# 2_4_LCD-CL24CR492-37B.net
KiCad netlist of a schematic drawn in Altium Designer
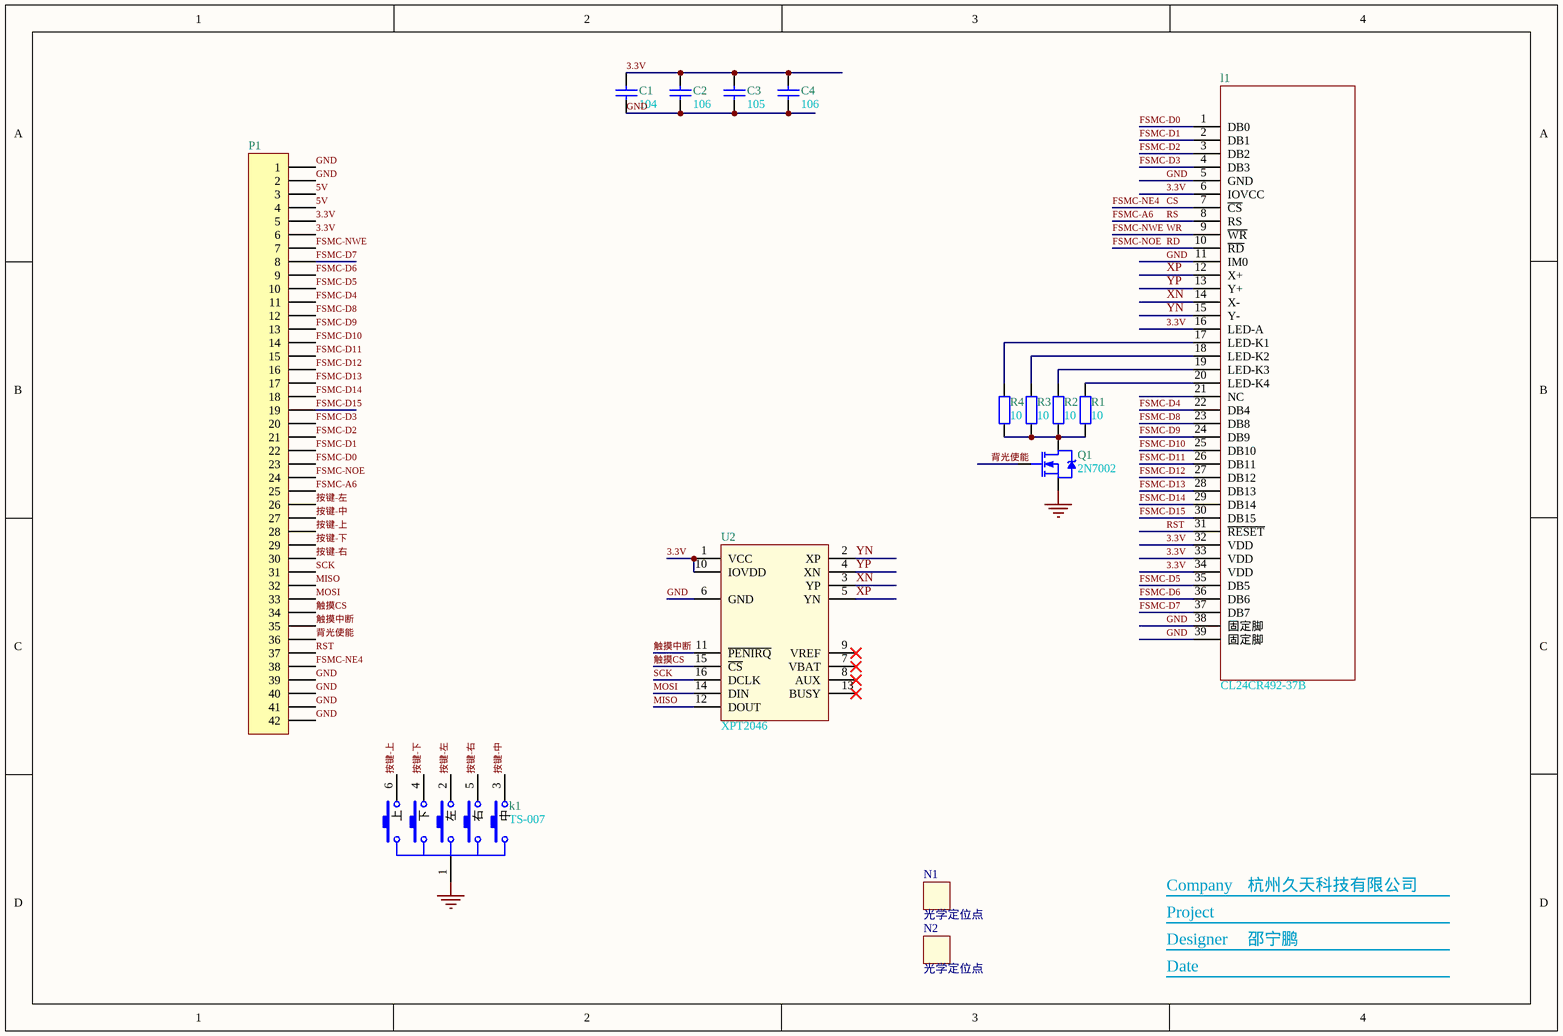
[diagram p0: 2.4寸LCD-CL24CR492-37B.SchDoc]

(export (version "E")
  (design (tool "Eeschema 10.0.6"))
  (components
    (comp (ref "C1")
      (value "104")
      (footprint "C-0603")
      (description "0805")
      (fields (field (name "PUBLISHER") "Altium Limited"))
      (libsource (lib "2电容-V1.0") (part "Cap-0603"))
    )
    (comp (ref "C2")
      (value "106")
      (footprint "C-0603")
      (description "0805")
      (fields (field (name "PUBLISHER") "Altium Limited"))
      (libsource (lib "2电容-V1.0") (part "Cap-0603"))
    )
    (comp (ref "C3")
      (value "105")
      (footprint "C-0603")
      (description "0805")
      (fields (field (name "PUBLISHER") "Altium Limited"))
      (libsource (lib "2电容-V1.0") (part "Cap-0603"))
    )
    (comp (ref "C4")
      (value "106")
      (footprint "C-0603")
      (description "0805")
      (fields (field (name "PUBLISHER") "Altium Limited"))
      (libsource (lib "2电容-V1.0") (part "Cap-0603"))
    )
    (comp (ref "k1")
      (value "TS-007")
      (footprint "TS-007")
      (description "五向开关")
      (libsource (lib "开关-V1") (part "TS-007"))
    )
    (comp (ref "l1")
      (value "CL24CR492-37B")
      (footprint "CL24CR492-37B")
      (libsource (lib "7显示屏-V1.0") (part "CL24CR492-37B"))
    )
    (comp (ref "N1") (value "光学定位点") (footprint "MARK-1mm-3mm") (libsource (lib "11其他元件-V1.0") (part "无引脚")))
    (comp (ref "N2") (value "光学定位点") (footprint "MARK-1mm-3mm") (libsource (lib "11其他元件-V1.0") (part "无引脚")))
    (comp (ref "P1")
      (value "~")
      (footprint "FPC-0.5mm_40P下接翻盖")
      (libsource (lib "5排针-V1.0") (part "MHDR1X42"))
    )
    (comp (ref "Q1") (value "2N7002") (footprint "SOT-23") (libsource (lib "4二极管-V1.1") (part "2N7002")))
    (comp (ref "R1")
      (value "10")
      (footprint "R-0603")
      (description "0603")
      (fields (field (name "PUBLISHER") "Altium Limited"))
      (libsource (lib "1电阻-V1.0") (part "Res2-0603"))
    )
    (comp (ref "R2")
      (value "10")
      (footprint "R-0603")
      (description "0603")
      (fields (field (name "PUBLISHER") "Altium Limited"))
      (libsource (lib "1电阻-V1.0") (part "Res2-0603"))
    )
    (comp (ref "R3")
      (value "10")
      (footprint "R-0603")
      (description "0603")
      (fields (field (name "PUBLISHER") "Altium Limited"))
      (libsource (lib "1电阻-V1.0") (part "Res2-0603"))
    )
    (comp (ref "R4")
      (value "10")
      (footprint "R-0603")
      (description "0603")
      (fields (field (name "PUBLISHER") "Altium Limited"))
      (libsource (lib "1电阻-V1.0") (part "Res2-0603"))
    )
    (comp (ref "U2") (value "XPT2046") (footprint "TSSOP-16") (libsource (lib "8集成电路-V1.1") (part "XPT2046")))
  )
  (nets
    (net (code "1") (name "/3.3V") (class "Default")
      (node (ref "C1") (pin "2") (pinfunction "2_2") (pintype "passive"))
      (node (ref "C2") (pin "2") (pinfunction "2_2") (pintype "passive"))
      (node (ref "C3") (pin "2") (pinfunction "2_2") (pintype "passive"))
      (node (ref "C4") (pin "2") (pinfunction "2_2") (pintype "passive"))
      (node (ref "P1") (pin "5") (pinfunction "5_5") (pintype "passive"))
      (node (ref "P1") (pin "6") (pinfunction "6_6") (pintype "passive"))
      (node (ref "U2") (pin "1") (pinfunction "VCC_1") (pintype "passive"))
      (node (ref "U2") (pin "10") (pinfunction "IOVDD_10") (pintype "passive"))
      (node (ref "l1") (pin "16") (pinfunction "LED-A_16") (pintype "passive"))
      (node (ref "l1") (pin "32") (pinfunction "VDD_32") (pintype "passive"))
      (node (ref "l1") (pin "33") (pinfunction "VDD_33") (pintype "passive"))
      (node (ref "l1") (pin "34") (pinfunction "VDD_34") (pintype "passive"))
      (node (ref "l1") (pin "6") (pinfunction "IOVCC_6") (pintype "passive"))
    )
    (net (code "2") (name "/5V") (class "Default")
      (node (ref "P1") (pin "3") (pinfunction "3_3") (pintype "passive"))
      (node (ref "P1") (pin "4") (pinfunction "4_4") (pintype "passive"))
    )
    (net (code "3") (name "/CS") (class "Default")
      (node (ref "P1") (pin "38") (pinfunction "38_38") (pintype "passive"))
      (node (ref "l1") (pin "7") (pinfunction "~{CS}_7") (pintype "passive"))
    )
    (net (code "4") (name "/FSMC-A6") (class "Default")
      (node (ref "P1") (pin "25") (pinfunction "25_25") (pintype "passive"))
      (node (ref "l1") (pin "8") (pinfunction "RS_8") (pintype "passive"))
    )
    (net (code "5") (name "/FSMC-D0") (class "Default")
      (node (ref "P1") (pin "23") (pinfunction "23_23") (pintype "passive"))
      (node (ref "l1") (pin "1") (pinfunction "DB0_1") (pintype "passive"))
    )
    (net (code "6") (name "/FSMC-D1") (class "Default")
      (node (ref "P1") (pin "22") (pinfunction "22_22") (pintype "passive"))
      (node (ref "l1") (pin "2") (pinfunction "DB1_2") (pintype "passive"))
    )
    (net (code "7") (name "/FSMC-D2") (class "Default")
      (node (ref "P1") (pin "21") (pinfunction "21_21") (pintype "passive"))
      (node (ref "l1") (pin "3") (pinfunction "DB2_3") (pintype "passive"))
    )
    (net (code "8") (name "/FSMC-D3") (class "Default")
      (node (ref "P1") (pin "20") (pinfunction "20_20") (pintype "passive"))
      (node (ref "l1") (pin "4") (pinfunction "DB3_4") (pintype "passive"))
    )
    (net (code "9") (name "/FSMC-D4") (class "Default")
      (node (ref "P1") (pin "11") (pinfunction "11_11") (pintype "passive"))
      (node (ref "l1") (pin "22") (pinfunction "DB4_22") (pintype "passive"))
    )
    (net (code "10") (name "/FSMC-D5") (class "Default")
      (node (ref "P1") (pin "10") (pinfunction "10_10") (pintype "passive"))
      (node (ref "l1") (pin "35") (pinfunction "DB5_35") (pintype "passive"))
    )
    (net (code "11") (name "/FSMC-D6") (class "Default")
      (node (ref "P1") (pin "9") (pinfunction "9_9") (pintype "passive"))
      (node (ref "l1") (pin "36") (pinfunction "DB6_36") (pintype "passive"))
    )
    (net (code "12") (name "/FSMC-D7") (class "Default")
      (node (ref "P1") (pin "8") (pinfunction "8_8") (pintype "passive"))
      (node (ref "l1") (pin "37") (pinfunction "DB7_37") (pintype "passive"))
    )
    (net (code "13") (name "/FSMC-D8") (class "Default")
      (node (ref "P1") (pin "12") (pinfunction "12_12") (pintype "passive"))
      (node (ref "l1") (pin "23") (pinfunction "DB8_23") (pintype "passive"))
    )
    (net (code "14") (name "/FSMC-D9") (class "Default")
      (node (ref "P1") (pin "13") (pinfunction "13_13") (pintype "passive"))
      (node (ref "l1") (pin "24") (pinfunction "DB9_24") (pintype "passive"))
    )
    (net (code "15") (name "/FSMC-D10") (class "Default")
      (node (ref "P1") (pin "14") (pinfunction "14_14") (pintype "passive"))
      (node (ref "l1") (pin "25") (pinfunction "DB10_25") (pintype "passive"))
    )
    (net (code "16") (name "/FSMC-D11") (class "Default")
      (node (ref "P1") (pin "15") (pinfunction "15_15") (pintype "passive"))
      (node (ref "l1") (pin "26") (pinfunction "DB11_26") (pintype "passive"))
    )
    (net (code "17") (name "/FSMC-D12") (class "Default")
      (node (ref "P1") (pin "16") (pinfunction "16_16") (pintype "passive"))
      (node (ref "l1") (pin "27") (pinfunction "DB12_27") (pintype "passive"))
    )
    (net (code "18") (name "/FSMC-D13") (class "Default")
      (node (ref "P1") (pin "17") (pinfunction "17_17") (pintype "passive"))
      (node (ref "l1") (pin "28") (pinfunction "DB13_28") (pintype "passive"))
    )
    (net (code "19") (name "/FSMC-D14") (class "Default")
      (node (ref "P1") (pin "18") (pinfunction "18_18") (pintype "passive"))
      (node (ref "l1") (pin "29") (pinfunction "DB14_29") (pintype "passive"))
    )
    (net (code "20") (name "/FSMC-D15") (class "Default")
      (node (ref "P1") (pin "19") (pinfunction "19_19") (pintype "passive"))
      (node (ref "l1") (pin "30") (pinfunction "DB15_30") (pintype "passive"))
    )
    (net (code "21") (name "/FSMC-NOE") (class "Default")
      (node (ref "P1") (pin "24") (pinfunction "24_24") (pintype "passive"))
      (node (ref "l1") (pin "10") (pinfunction "~{RD}_10") (pintype "passive"))
    )
    (net (code "22") (name "/FSMC-NWE") (class "Default")
      (node (ref "P1") (pin "7") (pinfunction "7_7") (pintype "passive"))
      (node (ref "l1") (pin "9") (pinfunction "~{WR}_9") (pintype "passive"))
    )
    (net (code "23") (name "/MISO") (class "Default")
      (node (ref "P1") (pin "32") (pinfunction "32_32") (pintype "passive"))
      (node (ref "U2") (pin "12") (pinfunction "DOUT_12") (pintype "passive"))
    )
    (net (code "24") (name "/MOSI") (class "Default")
      (node (ref "P1") (pin "33") (pinfunction "33_33") (pintype "passive"))
      (node (ref "U2") (pin "14") (pinfunction "DIN_14") (pintype "passive"))
    )
    (net (code "25") (name "/RST") (class "Default")
      (node (ref "P1") (pin "37") (pinfunction "37_37") (pintype "passive"))
      (node (ref "l1") (pin "31") (pinfunction "~{RESET}_31") (pintype "passive"))
    )
    (net (code "26") (name "/SCK") (class "Default")
      (node (ref "P1") (pin "31") (pinfunction "31_31") (pintype "passive"))
      (node (ref "U2") (pin "16") (pinfunction "DCLK_16") (pintype "passive"))
    )
    (net (code "27") (name "/XN") (class "Default")
      (node (ref "U2") (pin "3") (pinfunction "YP_3") (pintype "passive"))
      (node (ref "l1") (pin "14") (pinfunction "X-_14") (pintype "passive"))
    )
    (net (code "28") (name "/XP") (class "Default")
      (node (ref "U2") (pin "5") (pinfunction "YN_5") (pintype "passive"))
      (node (ref "l1") (pin "12") (pinfunction "X+_12") (pintype "passive"))
    )
    (net (code "29") (name "/YN") (class "Default")
      (node (ref "U2") (pin "2") (pinfunction "XP_2") (pintype "passive"))
      (node (ref "l1") (pin "15") (pinfunction "Y-_15") (pintype "passive"))
    )
    (net (code "30") (name "/YP") (class "Default")
      (node (ref "U2") (pin "4") (pinfunction "XN_4") (pintype "passive"))
      (node (ref "l1") (pin "13") (pinfunction "Y+_13") (pintype "passive"))
    )
    (net (code "31") (name "/按键-上") (class "Default")
      (node (ref "P1") (pin "28") (pinfunction "28_28") (pintype "passive"))
      (node (ref "k1") (pin "6") (pinfunction "上_6") (pintype "passive"))
    )
    (net (code "32") (name "/按键-下") (class "Default")
      (node (ref "P1") (pin "29") (pinfunction "29_29") (pintype "passive"))
      (node (ref "k1") (pin "4") (pinfunction "下_4") (pintype "passive"))
    )
    (net (code "33") (name "/按键-中") (class "Default")
      (node (ref "P1") (pin "27") (pinfunction "27_27") (pintype "passive"))
      (node (ref "k1") (pin "3") (pinfunction "中_3") (pintype "passive"))
    )
    (net (code "34") (name "/按键-右") (class "Default")
      (node (ref "P1") (pin "30") (pinfunction "30_30") (pintype "passive"))
      (node (ref "k1") (pin "5") (pinfunction "右_5") (pintype "passive"))
    )
    (net (code "35") (name "/按键-左") (class "Default")
      (node (ref "P1") (pin "26") (pinfunction "26_26") (pintype "passive"))
      (node (ref "k1") (pin "2") (pinfunction "左_2") (pintype "passive"))
    )
    (net (code "36") (name "/背光使能") (class "Default")
      (node (ref "P1") (pin "36") (pinfunction "36_36") (pintype "passive"))
      (node (ref "Q1") (pin "1") (pinfunction "G_1") (pintype "passive"))
    )
    (net (code "37") (name "/触摸CS") (class "Default")
      (node (ref "P1") (pin "34") (pinfunction "34_34") (pintype "passive"))
      (node (ref "U2") (pin "15") (pinfunction "~{CS}_15") (pintype "passive"))
    )
    (net (code "38") (name "/触摸中断") (class "Default")
      (node (ref "P1") (pin "35") (pinfunction "35_35") (pintype "passive"))
      (node (ref "U2") (pin "11") (pinfunction "~{PENIRQ}_11") (pintype "passive"))
    )
    (net (code "39") (name "GND") (class "Default")
      (node (ref "C1") (pin "1") (pinfunction "1_1") (pintype "passive"))
      (node (ref "C2") (pin "1") (pinfunction "1_1") (pintype "passive"))
      (node (ref "C3") (pin "1") (pinfunction "1_1") (pintype "passive"))
      (node (ref "C4") (pin "1") (pinfunction "1_1") (pintype "passive"))
      (node (ref "P1") (pin "1") (pinfunction "1_1") (pintype "passive"))
      (node (ref "P1") (pin "2") (pinfunction "2_2") (pintype "passive"))
      (node (ref "P1") (pin "39") (pinfunction "39_39") (pintype "passive"))
      (node (ref "P1") (pin "40") (pinfunction "40_40") (pintype "passive"))
      (node (ref "P1") (pin "41") (pinfunction "41_41") (pintype "passive"))
      (node (ref "P1") (pin "42") (pinfunction "42_42") (pintype "passive"))
      (node (ref "Q1") (pin "2") (pinfunction "S_2") (pintype "passive"))
      (node (ref "U2") (pin "6") (pinfunction "GND_6") (pintype "passive"))
      (node (ref "k1") (pin "1") (pinfunction "Common_1") (pintype "passive"))
      (node (ref "l1") (pin "11") (pinfunction "IM0_11") (pintype "passive"))
      (node (ref "l1") (pin "38") (pinfunction "固定脚_38") (pintype "passive"))
      (node (ref "l1") (pin "39") (pinfunction "固定脚_39") (pintype "passive"))
      (node (ref "l1") (pin "5") (pinfunction "GND_5") (pintype "passive"))
    )
    (net (code "40") (name "Net-(Q1-D)") (class "Default")
      (node (ref "Q1") (pin "3") (pinfunction "D_3") (pintype "passive"))
      (node (ref "R1") (pin "1") (pinfunction "1_1") (pintype "passive"))
      (node (ref "R2") (pin "1") (pinfunction "1_1") (pintype "passive"))
      (node (ref "R3") (pin "1") (pinfunction "1_1") (pintype "passive"))
      (node (ref "R4") (pin "1") (pinfunction "1_1") (pintype "passive"))
    )
    (net (code "41") (name "Net-(l1-LED-K1)") (class "Default")
      (node (ref "R4") (pin "2") (pinfunction "2_2") (pintype "passive"))
      (node (ref "l1") (pin "17") (pinfunction "LED-K1_17") (pintype "passive"))
    )
    (net (code "42") (name "Net-(l1-LED-K2)") (class "Default")
      (node (ref "R3") (pin "2") (pinfunction "2_2") (pintype "passive"))
      (node (ref "l1") (pin "18") (pinfunction "LED-K2_18") (pintype "passive"))
    )
    (net (code "43") (name "Net-(l1-LED-K3)") (class "Default")
      (node (ref "R2") (pin "2") (pinfunction "2_2") (pintype "passive"))
      (node (ref "l1") (pin "19") (pinfunction "LED-K3_19") (pintype "passive"))
    )
    (net (code "44") (name "Net-(l1-LED-K4)") (class "Default")
      (node (ref "R1") (pin "2") (pinfunction "2_2") (pintype "passive"))
      (node (ref "l1") (pin "20") (pinfunction "LED-K4_20") (pintype "passive"))
    )
    (net (code "45") (name "unconnected-(U2-AUX-Pad8)") (class "Default")
      (node (ref "U2") (pin "8") (pinfunction "AUX_8") (pintype "passive+no_connect"))
    )
    (net (code "46") (name "unconnected-(U2-BUSY-Pad13)") (class "Default")
      (node (ref "U2") (pin "13") (pinfunction "BUSY_13") (pintype "passive+no_connect"))
    )
    (net (code "47") (name "unconnected-(U2-VBAT-Pad7)") (class "Default")
      (node (ref "U2") (pin "7") (pinfunction "VBAT_7") (pintype "passive+no_connect"))
    )
    (net (code "48") (name "unconnected-(U2-VREF-Pad9)") (class "Default")
      (node (ref "U2") (pin "9") (pinfunction "VREF_9") (pintype "passive+no_connect"))
    )
    (net (code "49") (name "unconnected-(l1-NC-Pad21)") (class "Default")
      (node (ref "l1") (pin "21") (pinfunction "NC_21") (pintype "passive"))
    )
  )
)
